# ME433_PIC32_Schematic.net
KiCad netlist of a schematic drawn in EAGLE
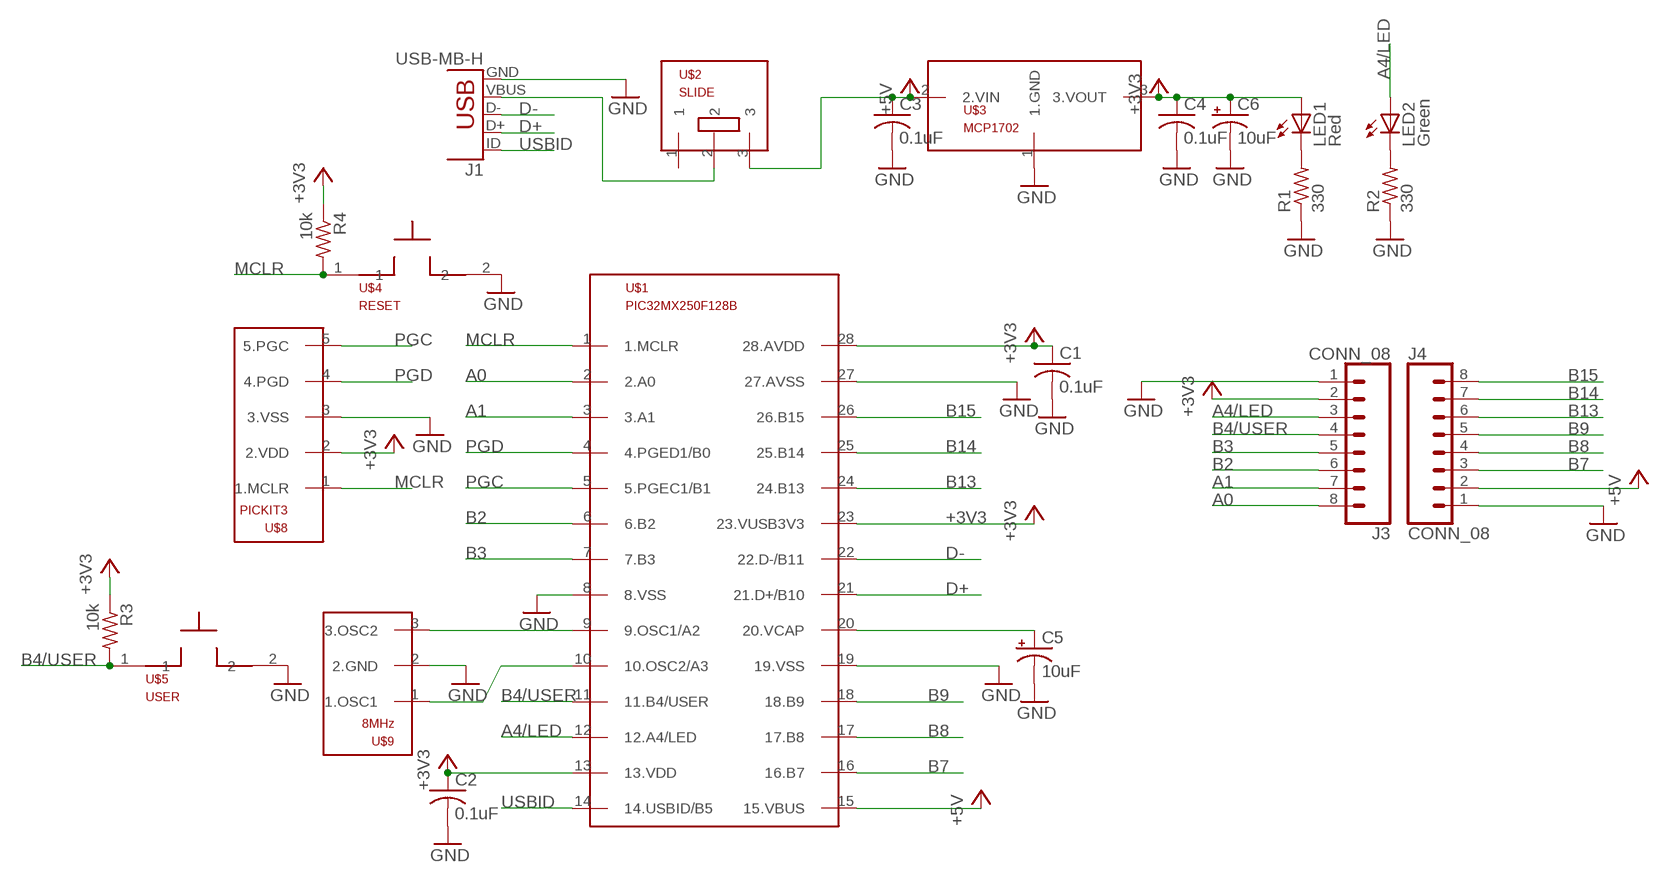
[diagram p0: schematic, sheet 1]

(export (version "E")
  (design (tool "Eeschema 10.0.6"))
  (components
    (comp (ref "C1")
      (value "0.1uF")
      (footprint "eagle-import:C025-025X050")
      (libsource (lib "eagle-import") (part "C-US025-025X050"))
    )
    (comp (ref "C2")
      (value "0.1uF")
      (footprint "eagle-import:C025-025X050")
      (libsource (lib "eagle-import") (part "C-US025-025X050"))
    )
    (comp (ref "C3")
      (value "0.1uF")
      (footprint "eagle-import:C025-025X050")
      (libsource (lib "eagle-import") (part "C-US025-025X050"))
    )
    (comp (ref "C4")
      (value "0.1uF")
      (footprint "eagle-import:C025-025X050")
      (libsource (lib "eagle-import") (part "C-US025-025X050"))
    )
    (comp (ref "C5")
      (value "10uF")
      (footprint "eagle-import:B45181B")
      (libsource (lib "eagle-import") (part "CPOL-USB45181B"))
    )
    (comp (ref "C6")
      (value "10uF")
      (footprint "eagle-import:B45181B")
      (libsource (lib "eagle-import") (part "CPOL-USB45181B"))
    )
    (comp (ref "J1")
      (value "USB-MB-H")
      (footprint "eagle-import:USB-MB-H")
      (libsource (lib "eagle-import") (part "USB-MB-H"))
    )
    (comp (ref "J3")
      (value "CONN_08")
      (footprint "eagle-import:1X08")
      (libsource (lib "eagle-import") (part "CONN_08"))
    )
    (comp (ref "J4")
      (value "CONN_08")
      (footprint "eagle-import:1X08")
      (libsource (lib "eagle-import") (part "CONN_08"))
    )
    (comp (ref "LED1")
      (value "Red")
      (footprint "eagle-import:LED3MM")
      (libsource (lib "eagle-import") (part "LED3MM"))
    )
    (comp (ref "LED2")
      (value "Green")
      (footprint "eagle-import:LED3MM")
      (libsource (lib "eagle-import") (part "LED3MM"))
    )
    (comp (ref "R1")
      (value "330")
      (footprint "eagle-import:0207_10")
      (libsource (lib "eagle-import") (part "R-US_0207/10"))
    )
    (comp (ref "R2")
      (value "330")
      (footprint "eagle-import:0207_10")
      (libsource (lib "eagle-import") (part "R-US_0207/10"))
    )
    (comp (ref "R3")
      (value "10k")
      (footprint "eagle-import:0207_10")
      (libsource (lib "eagle-import") (part "R-US_0207/10"))
    )
    (comp (ref "R4")
      (value "10k")
      (footprint "eagle-import:0207_10")
      (libsource (lib "eagle-import") (part "R-US_0207/10"))
    )
    (comp (ref "U$1")
      (value "PIC32MX250F128B")
      (footprint "eagle-import:DIL28-3")
      (libsource (lib "eagle-import") (part "PIC32MX250F128B"))
    )
    (comp (ref "U$2")
      (value "SLIDE")
      (footprint "eagle-import:SLIDE")
      (libsource (lib "eagle-import") (part "SLIDE"))
    )
    (comp (ref "U$3")
      (value "MCP1702")
      (footprint "eagle-import:TO92")
      (libsource (lib "eagle-import") (part "MCP1702"))
    )
    (comp (ref "U$4")
      (value "RESET")
      (footprint "eagle-import:PB")
      (libsource (lib "eagle-import") (part "PB"))
    )
    (comp (ref "U$5")
      (value "USER")
      (footprint "eagle-import:PB")
      (libsource (lib "eagle-import") (part "PB"))
    )
    (comp (ref "U$8")
      (value "PICKIT3")
      (footprint "eagle-import:1X05")
      (libsource (lib "eagle-import") (part "PICKIT3"))
    )
    (comp (ref "U$9")
      (value "8MHz")
      (footprint "eagle-import:OSC")
      (libsource (lib "eagle-import") (part "OSC"))
    )
  )
  (nets
    (net (code "1") (name "+3V3") (class "Default")
      (node (ref "C1") (pin "1") (pinfunction "1_1") (pintype "passive"))
      (node (ref "C2") (pin "1") (pinfunction "1_1") (pintype "passive"))
      (node (ref "C4") (pin "1") (pinfunction "1_1") (pintype "passive"))
      (node (ref "C6") (pin "+") (pinfunction "+_+") (pintype "passive"))
      (node (ref "J3") (pin "2") (pinfunction "2_2") (pintype "passive"))
      (node (ref "LED1") (pin "A") (pinfunction "A_A") (pintype "passive"))
      (node (ref "R3") (pin "1") (pinfunction "1_1") (pintype "passive"))
      (node (ref "R4") (pin "1") (pinfunction "1_1") (pintype "passive"))
      (node (ref "U$1") (pin "13") (pinfunction "13.VDD_13") (pintype "bidirectional"))
      (node (ref "U$1") (pin "23") (pinfunction "23.VUSB3V3_23") (pintype "bidirectional"))
      (node (ref "U$1") (pin "28") (pinfunction "28.AVDD_28") (pintype "bidirectional"))
      (node (ref "U$3") (pin "3") (pinfunction "3.VOUT_3") (pintype "bidirectional"))
      (node (ref "U$8") (pin "2") (pinfunction "2.VDD_2") (pintype "bidirectional"))
    )
    (net (code "2") (name "+5V") (class "Default")
      (node (ref "C3") (pin "1") (pinfunction "1_1") (pintype "passive"))
      (node (ref "J4") (pin "2") (pinfunction "2_2") (pintype "passive"))
      (node (ref "U$1") (pin "15") (pinfunction "15.VBUS_15") (pintype "bidirectional"))
      (node (ref "U$2") (pin "3") (pinfunction "3_3") (pintype "bidirectional"))
      (node (ref "U$3") (pin "2") (pinfunction "2.VIN_2") (pintype "bidirectional"))
    )
    (net (code "3") (name "/A0") (class "Default")
      (node (ref "J3") (pin "8") (pinfunction "8_8") (pintype "passive"))
      (node (ref "U$1") (pin "2") (pinfunction "2.A0_2") (pintype "bidirectional"))
    )
    (net (code "4") (name "/A1") (class "Default")
      (node (ref "J3") (pin "7") (pinfunction "7_7") (pintype "passive"))
      (node (ref "U$1") (pin "3") (pinfunction "3.A1_3") (pintype "bidirectional"))
    )
    (net (code "5") (name "/A4{slash}LED") (class "Default")
      (node (ref "J3") (pin "3") (pinfunction "3_3") (pintype "passive"))
      (node (ref "LED2") (pin "A") (pinfunction "A_A") (pintype "passive"))
      (node (ref "U$1") (pin "12") (pinfunction "12.A4/LED_12") (pintype "bidirectional"))
    )
    (net (code "6") (name "/B2") (class "Default")
      (node (ref "J3") (pin "6") (pinfunction "6_6") (pintype "passive"))
      (node (ref "U$1") (pin "6") (pinfunction "6.B2_6") (pintype "bidirectional"))
    )
    (net (code "7") (name "/B3") (class "Default")
      (node (ref "J3") (pin "5") (pinfunction "5_5") (pintype "passive"))
      (node (ref "U$1") (pin "7") (pinfunction "7.B3_7") (pintype "bidirectional"))
    )
    (net (code "8") (name "/B4{slash}USER") (class "Default")
      (node (ref "J3") (pin "4") (pinfunction "4_4") (pintype "passive"))
      (node (ref "R3") (pin "2") (pinfunction "2_2") (pintype "passive"))
      (node (ref "U$1") (pin "11") (pinfunction "11.B4/USER_11") (pintype "bidirectional"))
      (node (ref "U$5") (pin "1") (pinfunction "1_1") (pintype "bidirectional"))
    )
    (net (code "9") (name "/B7") (class "Default")
      (node (ref "J4") (pin "3") (pinfunction "3_3") (pintype "passive"))
      (node (ref "U$1") (pin "16") (pinfunction "16.B7_16") (pintype "bidirectional"))
    )
    (net (code "10") (name "/B8") (class "Default")
      (node (ref "J4") (pin "4") (pinfunction "4_4") (pintype "passive"))
      (node (ref "U$1") (pin "17") (pinfunction "17.B8_17") (pintype "bidirectional"))
    )
    (net (code "11") (name "/B9") (class "Default")
      (node (ref "J4") (pin "5") (pinfunction "5_5") (pintype "passive"))
      (node (ref "U$1") (pin "18") (pinfunction "18.B9_18") (pintype "bidirectional"))
    )
    (net (code "12") (name "/B13") (class "Default")
      (node (ref "J4") (pin "6") (pinfunction "6_6") (pintype "passive"))
      (node (ref "U$1") (pin "24") (pinfunction "24.B13_24") (pintype "bidirectional"))
    )
    (net (code "13") (name "/B14") (class "Default")
      (node (ref "J4") (pin "7") (pinfunction "7_7") (pintype "passive"))
      (node (ref "U$1") (pin "25") (pinfunction "25.B14_25") (pintype "bidirectional"))
    )
    (net (code "14") (name "/B15") (class "Default")
      (node (ref "J4") (pin "8") (pinfunction "8_8") (pintype "passive"))
      (node (ref "U$1") (pin "26") (pinfunction "26.B15_26") (pintype "bidirectional"))
    )
    (net (code "15") (name "/D+") (class "Default")
      (node (ref "J1") (pin "D+") (pinfunction "D+_D+") (pintype "bidirectional"))
      (node (ref "U$1") (pin "21") (pinfunction "21.D+/B10_21") (pintype "bidirectional"))
    )
    (net (code "16") (name "/D-") (class "Default")
      (node (ref "J1") (pin "D-") (pinfunction "D-_D-") (pintype "bidirectional"))
      (node (ref "U$1") (pin "22") (pinfunction "22.D-/B11_22") (pintype "bidirectional"))
    )
    (net (code "17") (name "/MCLR") (class "Default")
      (node (ref "R4") (pin "2") (pinfunction "2_2") (pintype "passive"))
      (node (ref "U$1") (pin "1") (pinfunction "1.MCLR_1") (pintype "bidirectional"))
      (node (ref "U$4") (pin "1") (pinfunction "1_1") (pintype "bidirectional"))
      (node (ref "U$8") (pin "1") (pinfunction "1.MCLR_1") (pintype "bidirectional"))
    )
    (net (code "18") (name "/PGC") (class "Default")
      (node (ref "U$1") (pin "5") (pinfunction "5.PGEC1/B1_5") (pintype "bidirectional"))
      (node (ref "U$8") (pin "5") (pinfunction "5.PGC_5") (pintype "bidirectional"))
    )
    (net (code "19") (name "/PGD") (class "Default")
      (node (ref "U$1") (pin "4") (pinfunction "4.PGED1/B0_4") (pintype "bidirectional"))
      (node (ref "U$8") (pin "4") (pinfunction "4.PGD_4") (pintype "bidirectional"))
    )
    (net (code "20") (name "/USBID") (class "Default")
      (node (ref "J1") (pin "ID") (pinfunction "ID_ID") (pintype "bidirectional"))
      (node (ref "U$1") (pin "14") (pinfunction "14.USBID/B5_14") (pintype "bidirectional"))
    )
    (net (code "21") (name "GND") (class "Default")
      (node (ref "C1") (pin "2") (pinfunction "2_2") (pintype "passive"))
      (node (ref "C2") (pin "2") (pinfunction "2_2") (pintype "passive"))
      (node (ref "C3") (pin "2") (pinfunction "2_2") (pintype "passive"))
      (node (ref "C4") (pin "2") (pinfunction "2_2") (pintype "passive"))
      (node (ref "C5") (pin "-") (pinfunction "-_-") (pintype "passive"))
      (node (ref "C6") (pin "-") (pinfunction "-_-") (pintype "passive"))
      (node (ref "J1") (pin "GND") (pinfunction "GND_GND") (pintype "bidirectional"))
      (node (ref "J3") (pin "1") (pinfunction "1_1") (pintype "passive"))
      (node (ref "J4") (pin "1") (pinfunction "1_1") (pintype "passive"))
      (node (ref "R1") (pin "1") (pinfunction "1_1") (pintype "passive"))
      (node (ref "R2") (pin "1") (pinfunction "1_1") (pintype "passive"))
      (node (ref "U$1") (pin "19") (pinfunction "19.VSS_19") (pintype "bidirectional"))
      (node (ref "U$1") (pin "27") (pinfunction "27.AVSS_27") (pintype "bidirectional"))
      (node (ref "U$1") (pin "8") (pinfunction "8.VSS_8") (pintype "bidirectional"))
      (node (ref "U$3") (pin "1") (pinfunction "1.GND_1") (pintype "bidirectional"))
      (node (ref "U$4") (pin "2") (pinfunction "2_2") (pintype "bidirectional"))
      (node (ref "U$5") (pin "2") (pinfunction "2_2") (pintype "bidirectional"))
      (node (ref "U$8") (pin "3") (pinfunction "3.VSS_3") (pintype "bidirectional"))
      (node (ref "U$9") (pin "2") (pinfunction "2.GND_2") (pintype "bidirectional"))
    )
    (net (code "22") (name "Net-(J1-PadVBUS)") (class "Default")
      (node (ref "J1") (pin "VBUS") (pinfunction "VBUS_VBUS") (pintype "bidirectional"))
      (node (ref "U$2") (pin "2") (pinfunction "2_2") (pintype "bidirectional"))
    )
    (net (code "23") (name "Net-(LED1-C)") (class "Default")
      (node (ref "LED1") (pin "K") (pinfunction "C_K") (pintype "passive"))
      (node (ref "R1") (pin "2") (pinfunction "2_2") (pintype "passive"))
    )
    (net (code "24") (name "Net-(LED2-C)") (class "Default")
      (node (ref "LED2") (pin "K") (pinfunction "C_K") (pintype "passive"))
      (node (ref "R2") (pin "2") (pinfunction "2_2") (pintype "passive"))
    )
    (net (code "25") (name "Net-(U$1-9.OSC1{slash}A2)") (class "Default")
      (node (ref "U$1") (pin "9") (pinfunction "9.OSC1/A2_9") (pintype "bidirectional"))
      (node (ref "U$9") (pin "3") (pinfunction "3.OSC2_3") (pintype "bidirectional"))
    )
    (net (code "26") (name "Net-(U$1-10.OSC2{slash}A3)") (class "Default")
      (node (ref "U$1") (pin "10") (pinfunction "10.OSC2/A3_10") (pintype "bidirectional"))
      (node (ref "U$9") (pin "1") (pinfunction "1.OSC1_1") (pintype "bidirectional"))
    )
    (net (code "27") (name "Net-(U$1-20.VCAP)") (class "Default")
      (node (ref "C5") (pin "+") (pinfunction "+_+") (pintype "passive"))
      (node (ref "U$1") (pin "20") (pinfunction "20.VCAP_20") (pintype "bidirectional"))
    )
    (net (code "28") (name "unconnected-(U$2-Pad1)") (class "Default")
      (node (ref "U$2") (pin "1") (pinfunction "1_1") (pintype "bidirectional"))
    )
  )
)
